# LFR_control_board_rev1.net
KiCad netlist of a schematic drawn in EAGLE
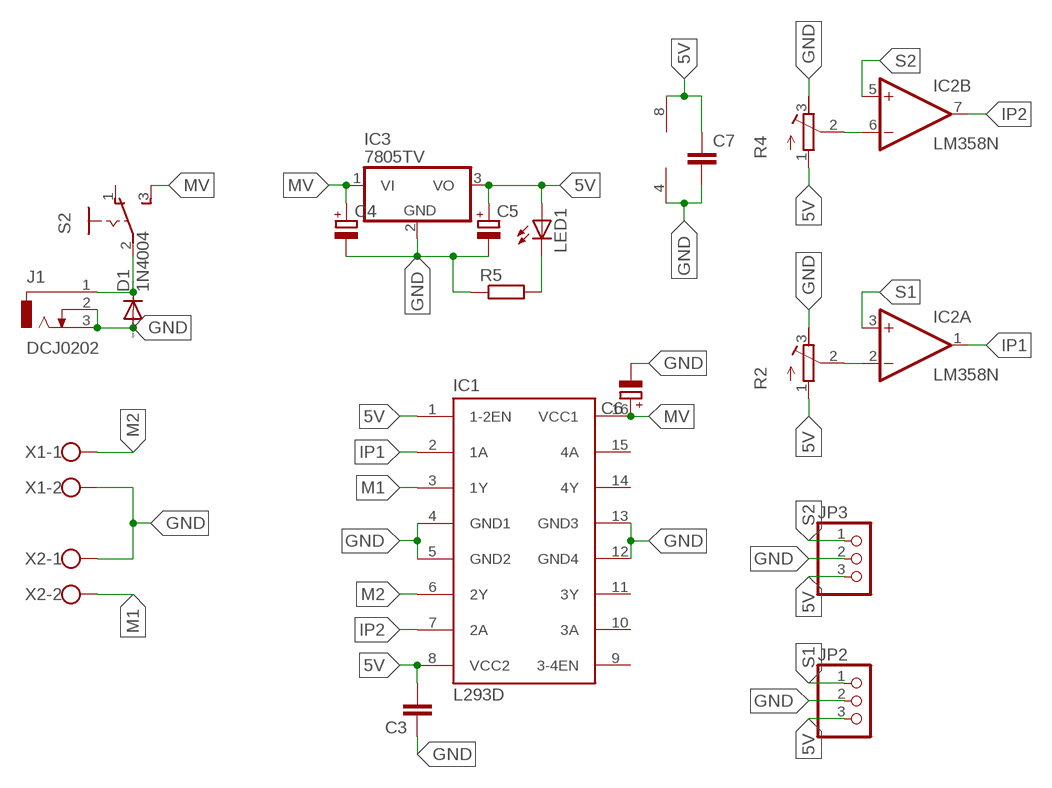
[diagram p0: schematic, sheet 1]

(export (version "E")
  (design (tool "Eeschema 10.0.6"))
  (components
    (comp (ref "C3")
      (value "C-EU025-025X050")
      (footprint "eagle-import:C025-025X050")
      (libsource (lib "eagle-import") (part "C-EU025-025X050"))
    )
    (comp (ref "C4")
      (value "CPOL-EUE2,5-6E")
      (footprint "eagle-import:E2,5-6E")
      (libsource (lib "eagle-import") (part "CPOL-EUE2,5-6E"))
    )
    (comp (ref "C5")
      (value "CPOL-EUE2,5-6E")
      (footprint "eagle-import:E2,5-6E")
      (libsource (lib "eagle-import") (part "CPOL-EUE2,5-6E"))
    )
    (comp (ref "C6")
      (value "CPOL-EUE5-10.5")
      (footprint "eagle-import:E5-10,5")
      (libsource (lib "eagle-import") (part "resistor_348_CPOL-EUE5-10.5"))
    )
    (comp (ref "C7")
      (value "C-EU025-025X050")
      (footprint "eagle-import:C025-025X050")
      (libsource (lib "eagle-import") (part "C-EU025-025X050"))
    )
    (comp (ref "D1")
      (value "1N4004")
      (footprint "eagle-import:DO41-10")
      (libsource (lib "eagle-import") (part "1N4004"))
    )
    (comp (ref "IC1")
      (value "L293D")
      (footprint "eagle-import:DIL16")
      (libsource (lib "eagle-import") (part "L293D"))
    )
    (comp (ref "IC2")
      (value "LM358N")
      (footprint "eagle-import:DIL08")
      (libsource (lib "eagle-import") (part "LM358N"))
    )
    (comp (ref "IC3")
      (value "7805TV")
      (footprint "eagle-import:TO220V")
      (libsource (lib "eagle-import") (part "78TV05"))
    )
    (comp (ref "J1")
      (value "DCJ0202")
      (footprint "eagle-import:DCJ0202")
      (libsource (lib "eagle-import") (part "DCJ0202"))
    )
    (comp (ref "JP2")
      (value "PINHD-1X3")
      (footprint "eagle-import:1X03")
      (libsource (lib "eagle-import") (part "PINHD-1X3"))
    )
    (comp (ref "JP3")
      (value "PINHD-1X3")
      (footprint "eagle-import:1X03")
      (libsource (lib "eagle-import") (part "PINHD-1X3"))
    )
    (comp (ref "LED1")
      (value "LED5MM")
      (footprint "eagle-import:LED5MM")
      (libsource (lib "eagle-import") (part "LED5MM"))
    )
    (comp (ref "R2")
      (value "R-TRIMM3296W")
      (footprint "eagle-import:RTRIM3296W")
      (libsource (lib "eagle-import") (part "R-TRIMM3296W"))
    )
    (comp (ref "R4")
      (value "R-TRIMM3296W")
      (footprint "eagle-import:RTRIM3296W")
      (libsource (lib "eagle-import") (part "R-TRIMM3296W"))
    )
    (comp (ref "R5")
      (value "R-EU_0207/10")
      (footprint "eagle-import:0207_10")
      (libsource (lib "eagle-import") (part "R-EU_0207/10"))
    )
    (comp (ref "S2")
      (value "255SB")
      (footprint "eagle-import:255SB")
      (libsource (lib "eagle-import") (part "255SB"))
    )
    (comp (ref "X1")
      (value "W237-102")
      (footprint "eagle-import:W237-102")
      (fields (field (name "MPN") "237-102"))
      (libsource (lib "eagle-import") (part "W237-102"))
    )
    (comp (ref "X2")
      (value "W237-102")
      (footprint "eagle-import:W237-102")
      (fields (field (name "MPN") "237-102"))
      (libsource (lib "eagle-import") (part "W237-102"))
    )
  )
  (nets
    (net (code "1") (name "5V") (class "Default")
      (node (ref "C3") (pin "2") (pinfunction "2_2") (pintype "passive"))
      (node (ref "C5") (pin "+") (pinfunction "+_+") (pintype "passive"))
      (node (ref "C7") (pin "1") (pinfunction "1_1") (pintype "passive"))
      (node (ref "IC1") (pin "1") (pinfunction "1-2EN_1") (pintype "input"))
      (node (ref "IC1") (pin "8") (pinfunction "VCC2_8") (pintype "power_in"))
      (node (ref "IC2") (pin "8") (pinfunction "V+_8") (pintype "power_in"))
      (node (ref "IC3") (pin "3") (pinfunction "VO_3") (pintype "passive"))
      (node (ref "JP2") (pin "3") (pinfunction "3_3") (pintype "passive"))
      (node (ref "JP3") (pin "3") (pinfunction "3_3") (pintype "passive"))
      (node (ref "LED1") (pin "A") (pinfunction "A_A") (pintype "passive"))
      (node (ref "R2") (pin "1") (pinfunction "A_1") (pintype "passive"))
      (node (ref "R4") (pin "1") (pinfunction "A_1") (pintype "passive"))
    )
    (net (code "2") (name "GND") (class "Default")
      (node (ref "C3") (pin "1") (pinfunction "1_1") (pintype "passive"))
      (node (ref "C4") (pin "-") (pinfunction "-_-") (pintype "passive"))
      (node (ref "C5") (pin "-") (pinfunction "-_-") (pintype "passive"))
      (node (ref "C6") (pin "-") (pinfunction "-_-") (pintype "passive"))
      (node (ref "C7") (pin "2") (pinfunction "2_2") (pintype "passive"))
      (node (ref "D1") (pin "A") (pinfunction "A_A") (pintype "passive"))
      (node (ref "IC1") (pin "12") (pinfunction "GND4_12") (pintype "power_in"))
      (node (ref "IC1") (pin "13") (pinfunction "GND3_13") (pintype "power_in"))
      (node (ref "IC1") (pin "4") (pinfunction "GND1_4") (pintype "power_in"))
      (node (ref "IC1") (pin "5") (pinfunction "GND2_5") (pintype "power_in"))
      (node (ref "IC2") (pin "4") (pinfunction "V-_4") (pintype "power_in"))
      (node (ref "IC3") (pin "2") (pinfunction "GND_2") (pintype "passive"))
      (node (ref "J1") (pin "2") (pinfunction "2_2") (pintype "passive"))
      (node (ref "J1") (pin "3") (pinfunction "3_3") (pintype "passive"))
      (node (ref "JP2") (pin "2") (pinfunction "2_2") (pintype "passive"))
      (node (ref "JP3") (pin "2") (pinfunction "2_2") (pintype "passive"))
      (node (ref "R2") (pin "3") (pinfunction "E_3") (pintype "passive"))
      (node (ref "R4") (pin "3") (pinfunction "E_3") (pintype "passive"))
      (node (ref "R5") (pin "1") (pinfunction "1_1") (pintype "passive"))
      (node (ref "X1") (pin "2") (pinfunction "KL_2") (pintype "passive"))
      (node (ref "X2") (pin "1") (pinfunction "KL_1") (pintype "passive"))
    )
    (net (code "3") (name "IP1") (class "Default")
      (node (ref "IC1") (pin "2") (pinfunction "1A_2") (pintype "input"))
      (node (ref "IC2") (pin "1") (pinfunction "OUT_1") (pintype "output"))
    )
    (net (code "4") (name "IP2") (class "Default")
      (node (ref "IC1") (pin "7") (pinfunction "2A_7") (pintype "input"))
      (node (ref "IC2") (pin "7") (pinfunction "OUT_7") (pintype "output"))
    )
    (net (code "5") (name "M1") (class "Default")
      (node (ref "IC1") (pin "3") (pinfunction "1Y_3") (pintype "output"))
      (node (ref "X2") (pin "2") (pinfunction "KL_2") (pintype "passive"))
    )
    (net (code "6") (name "M2") (class "Default")
      (node (ref "IC1") (pin "6") (pinfunction "2Y_6") (pintype "output"))
      (node (ref "X1") (pin "1") (pinfunction "KL_1") (pintype "passive"))
    )
    (net (code "7") (name "MV") (class "Default")
      (node (ref "C4") (pin "+") (pinfunction "+_+") (pintype "passive"))
      (node (ref "C6") (pin "+") (pinfunction "+_+") (pintype "passive"))
      (node (ref "IC1") (pin "16") (pinfunction "VCC1_16") (pintype "power_in"))
      (node (ref "IC3") (pin "1") (pinfunction "VI_1") (pintype "input"))
      (node (ref "S2") (pin "3") (pinfunction "S_3") (pintype "passive"))
    )
    (net (code "8") (name "Net-(IC2A--IN)") (class "Default")
      (node (ref "IC2") (pin "2") (pinfunction "-IN_2") (pintype "input"))
      (node (ref "R2") (pin "2") (pinfunction "S_2") (pintype "passive"))
    )
    (net (code "9") (name "Net-(IC2B--IN)") (class "Default")
      (node (ref "IC2") (pin "6") (pinfunction "-IN_6") (pintype "input"))
      (node (ref "R4") (pin "2") (pinfunction "S_2") (pintype "passive"))
    )
    (net (code "10") (name "Net-(LED1-C)") (class "Default")
      (node (ref "LED1") (pin "K") (pinfunction "C_K") (pintype "passive"))
      (node (ref "R5") (pin "2") (pinfunction "2_2") (pintype "passive"))
    )
    (net (code "11") (name "Net-(S2-P)") (class "Default")
      (node (ref "D1") (pin "C") (pinfunction "C_C") (pintype "passive"))
      (node (ref "J1") (pin "1") (pinfunction "1_1") (pintype "passive"))
      (node (ref "S2") (pin "2") (pinfunction "P_2") (pintype "passive"))
    )
    (net (code "12") (name "S1") (class "Default")
      (node (ref "IC2") (pin "3") (pinfunction "+IN_3") (pintype "input"))
      (node (ref "JP2") (pin "1") (pinfunction "1_1") (pintype "passive"))
    )
    (net (code "13") (name "S2") (class "Default")
      (node (ref "IC2") (pin "5") (pinfunction "+IN_5") (pintype "input"))
      (node (ref "JP3") (pin "1") (pinfunction "1_1") (pintype "passive"))
    )
    (net (code "14") (name "unconnected-(IC1-3-4EN-Pad9)") (class "Default")
      (node (ref "IC1") (pin "9") (pinfunction "3-4EN_9") (pintype "input"))
    )
    (net (code "15") (name "unconnected-(IC1-3A-Pad10)") (class "Default")
      (node (ref "IC1") (pin "10") (pinfunction "3A_10") (pintype "input"))
    )
    (net (code "16") (name "unconnected-(IC1-3Y-Pad11)") (class "Default")
      (node (ref "IC1") (pin "11") (pinfunction "3Y_11") (pintype "output"))
    )
    (net (code "17") (name "unconnected-(IC1-4A-Pad15)") (class "Default")
      (node (ref "IC1") (pin "15") (pinfunction "4A_15") (pintype "input"))
    )
    (net (code "18") (name "unconnected-(IC1-4Y-Pad14)") (class "Default")
      (node (ref "IC1") (pin "14") (pinfunction "4Y_14") (pintype "output"))
    )
    (net (code "19") (name "unconnected-(S2-O-Pad1)") (class "Default")
      (node (ref "S2") (pin "1") (pinfunction "O_1") (pintype "passive"))
    )
  )
)
